# School_System_PCB.net
KiCad netlist of a schematic drawn in EAGLE
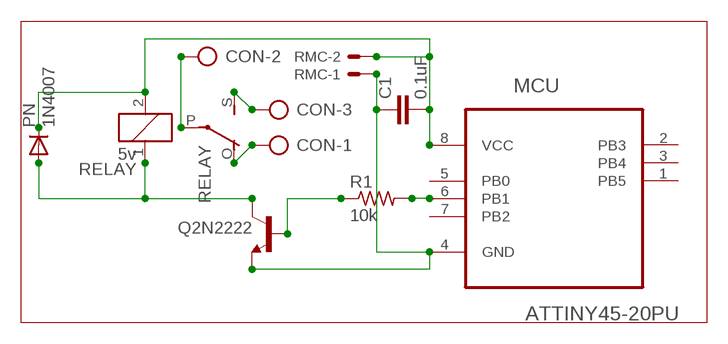
[diagram p0: schematic, sheet 1]

(export (version "E")
  (design (tool "Eeschema 10.0.6"))
  (components
    (comp (ref "C1")
      (value "0.1uF")
      (footprint "eagle-import:C2.5-3")
      (libsource (lib "eagle-import") (part "C2,5-3"))
    )
    (comp (ref "CON")
      (value "AK300/3")
      (footprint "eagle-import:AK300_3")
      (libsource (lib "eagle-import") (part "AK300/3"))
    )
    (comp (ref "MCU")
      (value "ATTINY45-20PU")
      (footprint "eagle-import:DIP254P762X533-8")
      (libsource (lib "eagle-import") (part "ATTINY45-20PU"))
    )
    (comp (ref "PN")
      (value "1N4007")
      (footprint "eagle-import:DO41-10")
      (libsource (lib "eagle-import") (part "1N4004"))
    )
    (comp (ref "Q2N2222")
      (value "2N2222-NPN-TO92-EBC")
      (footprint "eagle-import:TO92-EBC")
      (libsource (lib "eagle-import") (part "-NPN-TO92-EBC2N2222"))
    )
    (comp (ref "R1")
      (value "10k")
      (footprint "eagle-import:0204_7")
      (libsource (lib "eagle-import") (part "R-US_0204/7"))
    )
    (comp (ref "RELAY")
      (value "5v")
      (footprint "eagle-import:ZF112")
      (libsource (lib "eagle-import") (part "ZF112"))
    )
    (comp (ref "RMC")
      (value "22-23-2021")
      (footprint "eagle-import:22-23-2021")
      (fields (field (name "MF") "MOLEX"))
      (libsource (lib "eagle-import") (part "22-23-2021"))
    )
  )
  (nets
    (net (code "1") (name "Net-(CONA-KL)") (class "Default")
      (node (ref "CON") (pin "1") (pinfunction "KL_1") (pintype "passive"))
      (node (ref "RELAY") (pin "O") (pinfunction "O_O") (pintype "passive"))
    )
    (net (code "2") (name "Net-(CONB-KL)") (class "Default")
      (node (ref "CON") (pin "2") (pinfunction "KL_2") (pintype "passive"))
      (node (ref "RELAY") (pin "P") (pinfunction "P_P") (pintype "passive"))
    )
    (net (code "3") (name "Net-(CONC-KL)") (class "Default")
      (node (ref "CON") (pin "3") (pinfunction "KL_3") (pintype "passive"))
      (node (ref "RELAY") (pin "S") (pinfunction "S_S") (pintype "passive"))
    )
    (net (code "4") (name "Net-(MCU-GND)") (class "Default")
      (node (ref "C1") (pin "1") (pinfunction "1_1") (pintype "passive"))
      (node (ref "MCU") (pin "4") (pinfunction "GND_4") (pintype "passive"))
      (node (ref "Q2N2222") (pin "E") (pinfunction "E_E") (pintype "passive"))
      (node (ref "RMC") (pin "1") (pinfunction "S_1") (pintype "passive"))
    )
    (net (code "5") (name "Net-(MCU-PB1)") (class "Default")
      (node (ref "MCU") (pin "6") (pinfunction "PB1_6") (pintype "bidirectional"))
      (node (ref "R1") (pin "2") (pinfunction "2_2") (pintype "passive"))
    )
    (net (code "6") (name "Net-(MCU-VCC)") (class "Default")
      (node (ref "C1") (pin "2") (pinfunction "2_2") (pintype "passive"))
      (node (ref "MCU") (pin "8") (pinfunction "VCC_8") (pintype "power_in"))
      (node (ref "PN") (pin "C") (pinfunction "C_C") (pintype "passive"))
      (node (ref "RELAY") (pin "2") (pinfunction "2_2") (pintype "passive"))
      (node (ref "RMC") (pin "2") (pinfunction "S_2") (pintype "passive"))
    )
    (net (code "7") (name "Net-(PN-PadA)") (class "Default")
      (node (ref "PN") (pin "A") (pinfunction "A_A") (pintype "passive"))
      (node (ref "Q2N2222") (pin "C") (pinfunction "C_C") (pintype "passive"))
      (node (ref "RELAY") (pin "1") (pinfunction "1_1") (pintype "passive"))
    )
    (net (code "8") (name "Net-(Q2N2222-PadB)") (class "Default")
      (node (ref "Q2N2222") (pin "B") (pinfunction "B_B") (pintype "passive"))
      (node (ref "R1") (pin "1") (pinfunction "1_1") (pintype "passive"))
    )
    (net (code "9") (name "unconnected-(MCU-PB0-Pad5)") (class "Default")
      (node (ref "MCU") (pin "5") (pinfunction "PB0_5") (pintype "bidirectional"))
    )
    (net (code "10") (name "unconnected-(MCU-PB2-Pad7)") (class "Default")
      (node (ref "MCU") (pin "7") (pinfunction "PB2_7") (pintype "bidirectional"))
    )
    (net (code "11") (name "unconnected-(MCU-PB3-Pad2)") (class "Default")
      (node (ref "MCU") (pin "2") (pinfunction "PB3_2") (pintype "bidirectional"))
    )
    (net (code "12") (name "unconnected-(MCU-PB4-Pad3)") (class "Default")
      (node (ref "MCU") (pin "3") (pinfunction "PB4_3") (pintype "bidirectional"))
    )
    (net (code "13") (name "unconnected-(MCU-PB5-Pad1)") (class "Default")
      (node (ref "MCU") (pin "1") (pinfunction "PB5_1") (pintype "bidirectional"))
    )
  )
)
